# Daysuntil.net
KiCad netlist of a schematic drawn in EAGLE
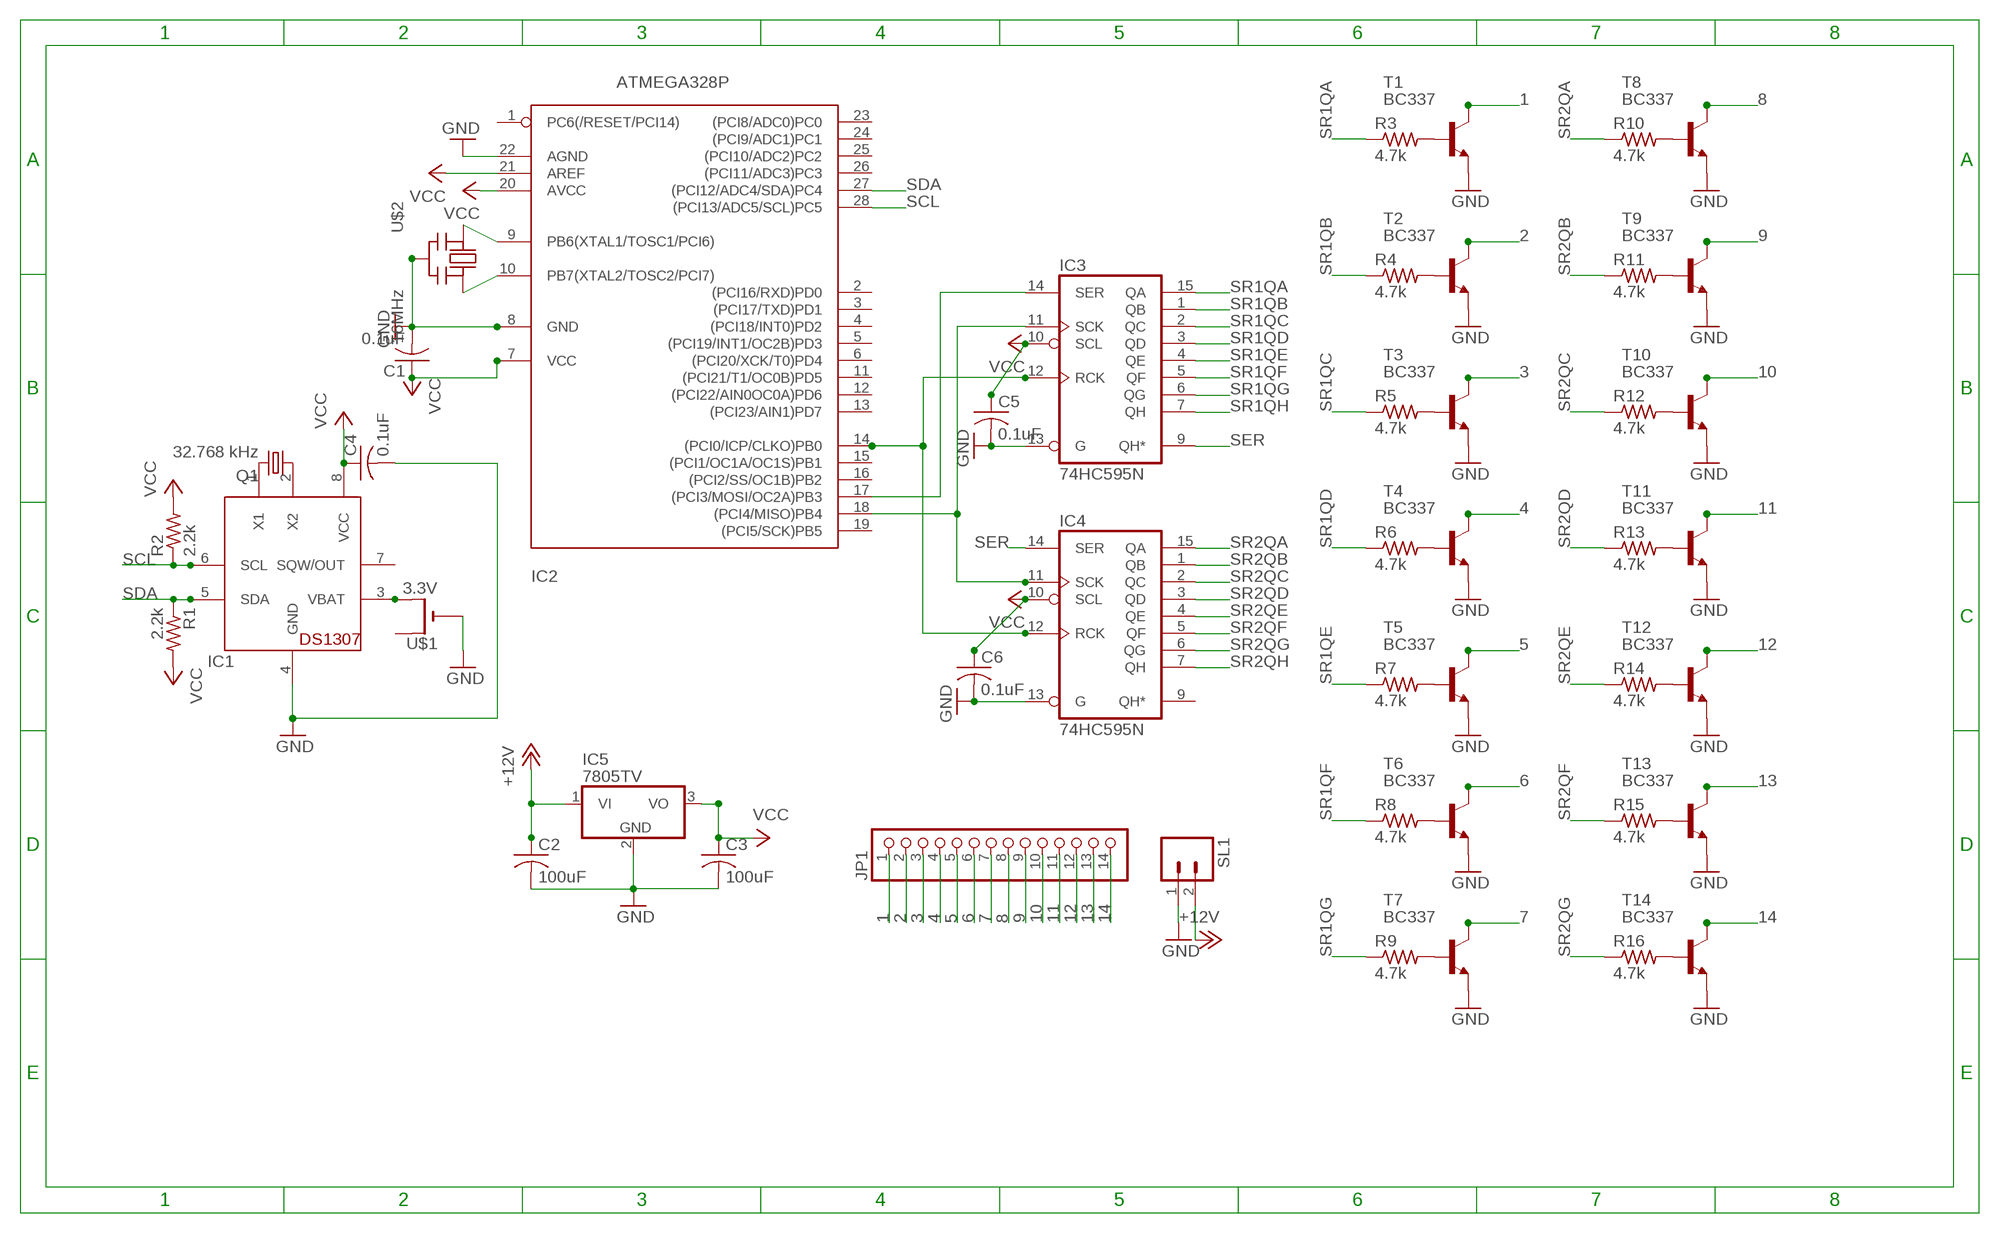
[diagram p0: schematic, sheet 1]

(export (version "E")
  (design (tool "Eeschema 10.0.6"))
  (components
    (comp (ref "C1")
      (value "0.1uF")
      (footprint "eagle-import:C025-030X050")
      (libsource (lib "eagle-import") (part "C-US025-030X050"))
    )
    (comp (ref "C2")
      (value "100uF")
      (footprint "eagle-import:C050-050X075")
      (libsource (lib "eagle-import") (part "C-US050-050X075"))
    )
    (comp (ref "C3")
      (value "100uF")
      (footprint "eagle-import:C050-050X075")
      (libsource (lib "eagle-import") (part "C-US050-050X075"))
    )
    (comp (ref "C4")
      (value "0.1uF")
      (footprint "eagle-import:C025-030X050")
      (libsource (lib "eagle-import") (part "C-US025-030X050"))
    )
    (comp (ref "C5")
      (value "0.1uF")
      (footprint "eagle-import:C025-030X050")
      (libsource (lib "eagle-import") (part "C-US025-030X050"))
    )
    (comp (ref "C6")
      (value "0.1uF")
      (footprint "eagle-import:C025-030X050")
      (libsource (lib "eagle-import") (part "C-US025-030X050"))
    )
    (comp (ref "IC1")
      (value "DS1307")
      (footprint "eagle-import:DIL08")
      (libsource (lib "eagle-import") (part "DS1307"))
    )
    (comp (ref "IC2")
      (value "ATMEGA328P")
      (footprint "eagle-import:DIL28-3")
      (libsource (lib "eagle-import") (part "ATMEGA168P-20"))
    )
    (comp (ref "IC3")
      (value "74HC595N")
      (footprint "eagle-import:DIL16")
      (libsource (lib "eagle-import") (part "74595NHC"))
    )
    (comp (ref "IC4")
      (value "74HC595N")
      (footprint "eagle-import:DIL16")
      (libsource (lib "eagle-import") (part "74595NHC"))
    )
    (comp (ref "IC5")
      (value "7805TV")
      (footprint "eagle-import:TO220V")
      (libsource (lib "eagle-import") (part "78TV05"))
    )
    (comp (ref "JP1")
      (value "PINHD-1X14")
      (footprint "eagle-import:1X14")
      (libsource (lib "eagle-import") (part "PINHD-1X14"))
    )
    (comp (ref "Q1")
      (value "32.768 kHz")
      (footprint "eagle-import:TC38H")
      (libsource (lib "eagle-import") (part "CRYSTALTC38H"))
    )
    (comp (ref "R1")
      (value "2.2k")
      (footprint "eagle-import:0309V")
      (libsource (lib "eagle-import") (part "R-US_0309/V"))
    )
    (comp (ref "R2")
      (value "2.2k")
      (footprint "eagle-import:0309V")
      (libsource (lib "eagle-import") (part "R-US_0309/V"))
    )
    (comp (ref "R3")
      (value "4.7k")
      (footprint "eagle-import:0309V")
      (libsource (lib "eagle-import") (part "R-US_0309/V"))
    )
    (comp (ref "R4")
      (value "4.7k")
      (footprint "eagle-import:0309V")
      (libsource (lib "eagle-import") (part "R-US_0309/V"))
    )
    (comp (ref "R5")
      (value "4.7k")
      (footprint "eagle-import:0309V")
      (libsource (lib "eagle-import") (part "R-US_0309/V"))
    )
    (comp (ref "R6")
      (value "4.7k")
      (footprint "eagle-import:0309V")
      (libsource (lib "eagle-import") (part "R-US_0309/V"))
    )
    (comp (ref "R7")
      (value "4.7k")
      (footprint "eagle-import:0309V")
      (libsource (lib "eagle-import") (part "R-US_0309/V"))
    )
    (comp (ref "R8")
      (value "4.7k")
      (footprint "eagle-import:0309V")
      (libsource (lib "eagle-import") (part "R-US_0309/V"))
    )
    (comp (ref "R9")
      (value "4.7k")
      (footprint "eagle-import:0309V")
      (libsource (lib "eagle-import") (part "R-US_0309/V"))
    )
    (comp (ref "R10")
      (value "4.7k")
      (footprint "eagle-import:0309V")
      (libsource (lib "eagle-import") (part "R-US_0309/V"))
    )
    (comp (ref "R11")
      (value "4.7k")
      (footprint "eagle-import:0309V")
      (libsource (lib "eagle-import") (part "R-US_0309/V"))
    )
    (comp (ref "R12")
      (value "4.7k")
      (footprint "eagle-import:0309V")
      (libsource (lib "eagle-import") (part "R-US_0309/V"))
    )
    (comp (ref "R13")
      (value "4.7k")
      (footprint "eagle-import:0309V")
      (libsource (lib "eagle-import") (part "R-US_0309/V"))
    )
    (comp (ref "R14")
      (value "4.7k")
      (footprint "eagle-import:0309V")
      (libsource (lib "eagle-import") (part "R-US_0309/V"))
    )
    (comp (ref "R15")
      (value "4.7k")
      (footprint "eagle-import:0309V")
      (libsource (lib "eagle-import") (part "R-US_0309/V"))
    )
    (comp (ref "R16")
      (value "4.7k")
      (footprint "eagle-import:0309V")
      (libsource (lib "eagle-import") (part "R-US_0309/V"))
    )
    (comp (ref "SL1")
      (value "M02")
      (footprint "eagle-import:02P")
      (libsource (lib "eagle-import") (part "M02"))
    )
    (comp (ref "T1")
      (value "BC337")
      (footprint "eagle-import:TO92")
      (libsource (lib "eagle-import") (part "BC337"))
    )
    (comp (ref "T2")
      (value "BC337")
      (footprint "eagle-import:TO92")
      (libsource (lib "eagle-import") (part "BC337"))
    )
    (comp (ref "T3")
      (value "BC337")
      (footprint "eagle-import:TO92")
      (libsource (lib "eagle-import") (part "BC337"))
    )
    (comp (ref "T4")
      (value "BC337")
      (footprint "eagle-import:TO92")
      (libsource (lib "eagle-import") (part "BC337"))
    )
    (comp (ref "T5")
      (value "BC337")
      (footprint "eagle-import:TO92")
      (libsource (lib "eagle-import") (part "BC337"))
    )
    (comp (ref "T6")
      (value "BC337")
      (footprint "eagle-import:TO92")
      (libsource (lib "eagle-import") (part "BC337"))
    )
    (comp (ref "T7")
      (value "BC337")
      (footprint "eagle-import:TO92")
      (libsource (lib "eagle-import") (part "BC337"))
    )
    (comp (ref "T8")
      (value "BC337")
      (footprint "eagle-import:TO92")
      (libsource (lib "eagle-import") (part "BC337"))
    )
    (comp (ref "T9")
      (value "BC337")
      (footprint "eagle-import:TO92")
      (libsource (lib "eagle-import") (part "BC337"))
    )
    (comp (ref "T10")
      (value "BC337")
      (footprint "eagle-import:TO92")
      (libsource (lib "eagle-import") (part "BC337"))
    )
    (comp (ref "T11")
      (value "BC337")
      (footprint "eagle-import:TO92")
      (libsource (lib "eagle-import") (part "BC337"))
    )
    (comp (ref "T12")
      (value "BC337")
      (footprint "eagle-import:TO92")
      (libsource (lib "eagle-import") (part "BC337"))
    )
    (comp (ref "T13")
      (value "BC337")
      (footprint "eagle-import:TO92")
      (libsource (lib "eagle-import") (part "BC337"))
    )
    (comp (ref "T14")
      (value "BC337")
      (footprint "eagle-import:TO92")
      (libsource (lib "eagle-import") (part "BC337"))
    )
    (comp (ref "U$1")
      (value "3.3V")
      (footprint "eagle-import:CR1220-THM")
      (libsource (lib "eagle-import") (part "CR1220THM"))
    )
    (comp (ref "U$2")
      (value "16MHz")
      (footprint "eagle-import:CERM_OSC")
      (libsource (lib "eagle-import") (part "CERMOSCILL-THM"))
    )
  )
  (nets
    (net (code "1") (name "+12V") (class "Default")
      (node (ref "C2") (pin "1") (pinfunction "1_1") (pintype "passive"))
      (node (ref "IC5") (pin "1") (pinfunction "VI_1") (pintype "input"))
      (node (ref "SL1") (pin "2") (pinfunction "2_2") (pintype "passive"))
    )
    (net (code "2") (name "/1") (class "Default")
      (node (ref "JP1") (pin "1") (pinfunction "1_1") (pintype "passive"))
      (node (ref "T1") (pin "3") (pinfunction "C_3") (pintype "passive"))
    )
    (net (code "3") (name "/2") (class "Default")
      (node (ref "JP1") (pin "2") (pinfunction "2_2") (pintype "passive"))
      (node (ref "T2") (pin "3") (pinfunction "C_3") (pintype "passive"))
    )
    (net (code "4") (name "/3") (class "Default")
      (node (ref "JP1") (pin "3") (pinfunction "3_3") (pintype "passive"))
      (node (ref "T3") (pin "3") (pinfunction "C_3") (pintype "passive"))
    )
    (net (code "5") (name "/4") (class "Default")
      (node (ref "JP1") (pin "4") (pinfunction "4_4") (pintype "passive"))
      (node (ref "T4") (pin "3") (pinfunction "C_3") (pintype "passive"))
    )
    (net (code "6") (name "/5") (class "Default")
      (node (ref "JP1") (pin "5") (pinfunction "5_5") (pintype "passive"))
      (node (ref "T5") (pin "3") (pinfunction "C_3") (pintype "passive"))
    )
    (net (code "7") (name "/6") (class "Default")
      (node (ref "JP1") (pin "6") (pinfunction "6_6") (pintype "passive"))
      (node (ref "T6") (pin "3") (pinfunction "C_3") (pintype "passive"))
    )
    (net (code "8") (name "/7") (class "Default")
      (node (ref "JP1") (pin "7") (pinfunction "7_7") (pintype "passive"))
      (node (ref "T7") (pin "3") (pinfunction "C_3") (pintype "passive"))
    )
    (net (code "9") (name "/8") (class "Default")
      (node (ref "JP1") (pin "8") (pinfunction "8_8") (pintype "passive"))
      (node (ref "T8") (pin "3") (pinfunction "C_3") (pintype "passive"))
    )
    (net (code "10") (name "/9") (class "Default")
      (node (ref "JP1") (pin "9") (pinfunction "9_9") (pintype "passive"))
      (node (ref "T9") (pin "3") (pinfunction "C_3") (pintype "passive"))
    )
    (net (code "11") (name "/10") (class "Default")
      (node (ref "JP1") (pin "10") (pinfunction "10_10") (pintype "passive"))
      (node (ref "T10") (pin "3") (pinfunction "C_3") (pintype "passive"))
    )
    (net (code "12") (name "/11") (class "Default")
      (node (ref "JP1") (pin "11") (pinfunction "11_11") (pintype "passive"))
      (node (ref "T11") (pin "3") (pinfunction "C_3") (pintype "passive"))
    )
    (net (code "13") (name "/12") (class "Default")
      (node (ref "JP1") (pin "12") (pinfunction "12_12") (pintype "passive"))
      (node (ref "T12") (pin "3") (pinfunction "C_3") (pintype "passive"))
    )
    (net (code "14") (name "/13") (class "Default")
      (node (ref "JP1") (pin "13") (pinfunction "13_13") (pintype "passive"))
      (node (ref "T13") (pin "3") (pinfunction "C_3") (pintype "passive"))
    )
    (net (code "15") (name "/14") (class "Default")
      (node (ref "JP1") (pin "14") (pinfunction "14_14") (pintype "passive"))
      (node (ref "T14") (pin "3") (pinfunction "C_3") (pintype "passive"))
    )
    (net (code "16") (name "/SCL") (class "Default")
      (node (ref "IC1") (pin "6") (pinfunction "SCL_6") (pintype "bidirectional"))
      (node (ref "IC2") (pin "28") (pinfunction "(PCI13/ADC5/SCL)PC5_28") (pintype "bidirectional"))
      (node (ref "R2") (pin "1") (pinfunction "1_1") (pintype "passive"))
    )
    (net (code "17") (name "/SDA") (class "Default")
      (node (ref "IC1") (pin "5") (pinfunction "SDA_5") (pintype "bidirectional"))
      (node (ref "IC2") (pin "27") (pinfunction "(PCI12/ADC4/SDA)PC4_27") (pintype "bidirectional"))
      (node (ref "R1") (pin "1") (pinfunction "1_1") (pintype "passive"))
    )
    (net (code "18") (name "/SER") (class "Default")
      (node (ref "IC3") (pin "9") (pinfunction "QH*_9") (pintype "tri_state"))
      (node (ref "IC4") (pin "14") (pinfunction "SER_14") (pintype "input"))
    )
    (net (code "19") (name "/SR1QA") (class "Default")
      (node (ref "IC3") (pin "15") (pinfunction "QA_15") (pintype "tri_state"))
      (node (ref "R3") (pin "1") (pinfunction "1_1") (pintype "passive"))
    )
    (net (code "20") (name "/SR1QB") (class "Default")
      (node (ref "IC3") (pin "1") (pinfunction "QB_1") (pintype "tri_state"))
      (node (ref "R4") (pin "1") (pinfunction "1_1") (pintype "passive"))
    )
    (net (code "21") (name "/SR1QC") (class "Default")
      (node (ref "IC3") (pin "2") (pinfunction "QC_2") (pintype "tri_state"))
      (node (ref "R5") (pin "1") (pinfunction "1_1") (pintype "passive"))
    )
    (net (code "22") (name "/SR1QD") (class "Default")
      (node (ref "IC3") (pin "3") (pinfunction "QD_3") (pintype "tri_state"))
      (node (ref "R6") (pin "1") (pinfunction "1_1") (pintype "passive"))
    )
    (net (code "23") (name "/SR1QE") (class "Default")
      (node (ref "IC3") (pin "4") (pinfunction "QE_4") (pintype "tri_state"))
      (node (ref "R7") (pin "1") (pinfunction "1_1") (pintype "passive"))
    )
    (net (code "24") (name "/SR1QF") (class "Default")
      (node (ref "IC3") (pin "5") (pinfunction "QF_5") (pintype "tri_state"))
      (node (ref "R8") (pin "1") (pinfunction "1_1") (pintype "passive"))
    )
    (net (code "25") (name "/SR1QG") (class "Default")
      (node (ref "IC3") (pin "6") (pinfunction "QG_6") (pintype "tri_state"))
      (node (ref "R9") (pin "1") (pinfunction "1_1") (pintype "passive"))
    )
    (net (code "26") (name "/SR1QH") (class "Default")
      (node (ref "IC3") (pin "7") (pinfunction "QH_7") (pintype "tri_state"))
    )
    (net (code "27") (name "/SR2QA") (class "Default")
      (node (ref "IC4") (pin "15") (pinfunction "QA_15") (pintype "tri_state"))
      (node (ref "R10") (pin "1") (pinfunction "1_1") (pintype "passive"))
    )
    (net (code "28") (name "/SR2QB") (class "Default")
      (node (ref "IC4") (pin "1") (pinfunction "QB_1") (pintype "tri_state"))
      (node (ref "R11") (pin "1") (pinfunction "1_1") (pintype "passive"))
    )
    (net (code "29") (name "/SR2QC") (class "Default")
      (node (ref "IC4") (pin "2") (pinfunction "QC_2") (pintype "tri_state"))
      (node (ref "R12") (pin "1") (pinfunction "1_1") (pintype "passive"))
    )
    (net (code "30") (name "/SR2QD") (class "Default")
      (node (ref "IC4") (pin "3") (pinfunction "QD_3") (pintype "tri_state"))
      (node (ref "R13") (pin "1") (pinfunction "1_1") (pintype "passive"))
    )
    (net (code "31") (name "/SR2QE") (class "Default")
      (node (ref "IC4") (pin "4") (pinfunction "QE_4") (pintype "tri_state"))
      (node (ref "R14") (pin "1") (pinfunction "1_1") (pintype "passive"))
    )
    (net (code "32") (name "/SR2QF") (class "Default")
      (node (ref "IC4") (pin "5") (pinfunction "QF_5") (pintype "tri_state"))
      (node (ref "R15") (pin "1") (pinfunction "1_1") (pintype "passive"))
    )
    (net (code "33") (name "/SR2QG") (class "Default")
      (node (ref "IC4") (pin "6") (pinfunction "QG_6") (pintype "tri_state"))
      (node (ref "R16") (pin "1") (pinfunction "1_1") (pintype "passive"))
    )
    (net (code "34") (name "/SR2QH") (class "Default")
      (node (ref "IC4") (pin "7") (pinfunction "QH_7") (pintype "tri_state"))
    )
    (net (code "35") (name "GND") (class "Default")
      (node (ref "C1") (pin "2") (pinfunction "2_2") (pintype "passive"))
      (node (ref "C2") (pin "2") (pinfunction "2_2") (pintype "passive"))
      (node (ref "C3") (pin "2") (pinfunction "2_2") (pintype "passive"))
      (node (ref "C4") (pin "2") (pinfunction "2_2") (pintype "passive"))
      (node (ref "C5") (pin "2") (pinfunction "2_2") (pintype "passive"))
      (node (ref "C6") (pin "2") (pinfunction "2_2") (pintype "passive"))
      (node (ref "IC1") (pin "4") (pinfunction "GND_4") (pintype "power_in"))
      (node (ref "IC2") (pin "22") (pinfunction "AGND_22") (pintype "bidirectional"))
      (node (ref "IC2") (pin "8") (pinfunction "GND_8") (pintype "bidirectional"))
      (node (ref "IC3") (pin "13") (pinfunction "G_13") (pintype "input"))
      (node (ref "IC4") (pin "13") (pinfunction "G_13") (pintype "input"))
      (node (ref "IC5") (pin "2") (pinfunction "GND_2") (pintype "passive"))
      (node (ref "SL1") (pin "1") (pinfunction "1_1") (pintype "passive"))
      (node (ref "T1") (pin "1") (pinfunction "E_1") (pintype "passive"))
      (node (ref "T10") (pin "1") (pinfunction "E_1") (pintype "passive"))
      (node (ref "T11") (pin "1") (pinfunction "E_1") (pintype "passive"))
      (node (ref "T12") (pin "1") (pinfunction "E_1") (pintype "passive"))
      (node (ref "T13") (pin "1") (pinfunction "E_1") (pintype "passive"))
      (node (ref "T14") (pin "1") (pinfunction "E_1") (pintype "passive"))
      (node (ref "T2") (pin "1") (pinfunction "E_1") (pintype "passive"))
      (node (ref "T3") (pin "1") (pinfunction "E_1") (pintype "passive"))
      (node (ref "T4") (pin "1") (pinfunction "E_1") (pintype "passive"))
      (node (ref "T5") (pin "1") (pinfunction "E_1") (pintype "passive"))
      (node (ref "T6") (pin "1") (pinfunction "E_1") (pintype "passive"))
      (node (ref "T7") (pin "1") (pinfunction "E_1") (pintype "passive"))
      (node (ref "T8") (pin "1") (pinfunction "E_1") (pintype "passive"))
      (node (ref "T9") (pin "1") (pinfunction "E_1") (pintype "passive"))
      (node (ref "U$1") (pin "-") (pinfunction "-_-") (pintype "passive"))
      (node (ref "U$2") (pin "P$2") (pinfunction "GND_P$2") (pintype "bidirectional"))
    )
    (net (code "36") (name "Net-(IC1-VBAT)") (class "Default")
      (node (ref "IC1") (pin "3") (pinfunction "VBAT_3") (pintype "power_in"))
      (node (ref "U$1") (pin "+2") (pinfunction "+1_+2") (pintype "passive"))
    )
    (net (code "37") (name "Net-(IC1-X1)") (class "Default")
      (node (ref "IC1") (pin "1") (pinfunction "X1_1") (pintype "passive"))
      (node (ref "Q1") (pin "2") (pinfunction "2_2") (pintype "passive"))
    )
    (net (code "38") (name "Net-(IC1-X2)") (class "Default")
      (node (ref "IC1") (pin "2") (pinfunction "X2_2") (pintype "passive"))
      (node (ref "Q1") (pin "1") (pinfunction "1_1") (pintype "passive"))
    )
    (net (code "39") (name "Net-(IC2-(PCI0{slash}ICP{slash}CLKO)PB0)") (class "Default")
      (node (ref "IC2") (pin "14") (pinfunction "(PCI0/ICP/CLKO)PB0_14") (pintype "bidirectional"))
      (node (ref "IC3") (pin "12") (pinfunction "RCK_12") (pintype "input"))
      (node (ref "IC4") (pin "12") (pinfunction "RCK_12") (pintype "input"))
    )
    (net (code "40") (name "Net-(IC2-(PCI3{slash}MOSI{slash}OC2A)PB3)") (class "Default")
      (node (ref "IC2") (pin "17") (pinfunction "(PCI3/MOSI/OC2A)PB3_17") (pintype "bidirectional"))
      (node (ref "IC3") (pin "14") (pinfunction "SER_14") (pintype "input"))
    )
    (net (code "41") (name "Net-(IC2-(PCI4{slash}MISO)PB4)") (class "Default")
      (node (ref "IC2") (pin "18") (pinfunction "(PCI4/MISO)PB4_18") (pintype "bidirectional"))
      (node (ref "IC3") (pin "11") (pinfunction "SCK_11") (pintype "input"))
      (node (ref "IC4") (pin "11") (pinfunction "SCK_11") (pintype "input"))
    )
    (net (code "42") (name "Net-(IC2-PB6(XTAL1{slash}TOSC1{slash}PCI6))") (class "Default")
      (node (ref "IC2") (pin "9") (pinfunction "PB6(XTAL1/TOSC1/PCI6)_9") (pintype "bidirectional"))
      (node (ref "U$2") (pin "P$1") (pinfunction "IN_P$1") (pintype "bidirectional"))
    )
    (net (code "43") (name "Net-(IC2-PB7(XTAL2{slash}TOSC2{slash}PCI7))") (class "Default")
      (node (ref "IC2") (pin "10") (pinfunction "PB7(XTAL2/TOSC2/PCI7)_10") (pintype "bidirectional"))
      (node (ref "U$2") (pin "P$3") (pinfunction "OUT_P$3") (pintype "bidirectional"))
    )
    (net (code "44") (name "Net-(T1-B)") (class "Default")
      (node (ref "R3") (pin "2") (pinfunction "2_2") (pintype "passive"))
      (node (ref "T1") (pin "2") (pinfunction "B_2") (pintype "passive"))
    )
    (net (code "45") (name "Net-(T2-B)") (class "Default")
      (node (ref "R4") (pin "2") (pinfunction "2_2") (pintype "passive"))
      (node (ref "T2") (pin "2") (pinfunction "B_2") (pintype "passive"))
    )
    (net (code "46") (name "Net-(T3-B)") (class "Default")
      (node (ref "R5") (pin "2") (pinfunction "2_2") (pintype "passive"))
      (node (ref "T3") (pin "2") (pinfunction "B_2") (pintype "passive"))
    )
    (net (code "47") (name "Net-(T4-B)") (class "Default")
      (node (ref "R6") (pin "2") (pinfunction "2_2") (pintype "passive"))
      (node (ref "T4") (pin "2") (pinfunction "B_2") (pintype "passive"))
    )
    (net (code "48") (name "Net-(T5-B)") (class "Default")
      (node (ref "R7") (pin "2") (pinfunction "2_2") (pintype "passive"))
      (node (ref "T5") (pin "2") (pinfunction "B_2") (pintype "passive"))
    )
    (net (code "49") (name "Net-(T6-B)") (class "Default")
      (node (ref "R8") (pin "2") (pinfunction "2_2") (pintype "passive"))
      (node (ref "T6") (pin "2") (pinfunction "B_2") (pintype "passive"))
    )
    (net (code "50") (name "Net-(T7-B)") (class "Default")
      (node (ref "R9") (pin "2") (pinfunction "2_2") (pintype "passive"))
      (node (ref "T7") (pin "2") (pinfunction "B_2") (pintype "passive"))
    )
    (net (code "51") (name "Net-(T8-B)") (class "Default")
      (node (ref "R10") (pin "2") (pinfunction "2_2") (pintype "passive"))
      (node (ref "T8") (pin "2") (pinfunction "B_2") (pintype "passive"))
    )
    (net (code "52") (name "Net-(T9-B)") (class "Default")
      (node (ref "R11") (pin "2") (pinfunction "2_2") (pintype "passive"))
      (node (ref "T9") (pin "2") (pinfunction "B_2") (pintype "passive"))
    )
    (net (code "53") (name "Net-(T10-B)") (class "Default")
      (node (ref "R12") (pin "2") (pinfunction "2_2") (pintype "passive"))
      (node (ref "T10") (pin "2") (pinfunction "B_2") (pintype "passive"))
    )
    (net (code "54") (name "Net-(T11-B)") (class "Default")
      (node (ref "R13") (pin "2") (pinfunction "2_2") (pintype "passive"))
      (node (ref "T11") (pin "2") (pinfunction "B_2") (pintype "passive"))
    )
    (net (code "55") (name "Net-(T12-B)") (class "Default")
      (node (ref "R14") (pin "2") (pinfunction "2_2") (pintype "passive"))
      (node (ref "T12") (pin "2") (pinfunction "B_2") (pintype "passive"))
    )
    (net (code "56") (name "Net-(T13-B)") (class "Default")
      (node (ref "R15") (pin "2") (pinfunction "2_2") (pintype "passive"))
      (node (ref "T13") (pin "2") (pinfunction "B_2") (pintype "passive"))
    )
    (net (code "57") (name "Net-(T14-B)") (class "Default")
      (node (ref "R16") (pin "2") (pinfunction "2_2") (pintype "passive"))
      (node (ref "T14") (pin "2") (pinfunction "B_2") (pintype "passive"))
    )
    (net (code "58") (name "VCC") (class "Default")
      (node (ref "C1") (pin "1") (pinfunction "1_1") (pintype "passive"))
      (node (ref "C3") (pin "1") (pinfunction "1_1") (pintype "passive"))
      (node (ref "C4") (pin "1") (pinfunction "1_1") (pintype "passive"))
      (node (ref "C5") (pin "1") (pinfunction "1_1") (pintype "passive"))
      (node (ref "C6") (pin "1") (pinfunction "1_1") (pintype "passive"))
      (node (ref "IC1") (pin "8") (pinfunction "VCC_8") (pintype "power_in"))
      (node (ref "IC2") (pin "20") (pinfunction "AVCC_20") (pintype "bidirectional"))
      (node (ref "IC2") (pin "21") (pinfunction "AREF_21") (pintype "bidirectional"))
      (node (ref "IC2") (pin "7") (pinfunction "VCC_7") (pintype "bidirectional"))
      (node (ref "IC3") (pin "10") (pinfunction "SCL_10") (pintype "input"))
      (node (ref "IC4") (pin "10") (pinfunction "SCL_10") (pintype "input"))
      (node (ref "IC5") (pin "3") (pinfunction "VO_3") (pintype "passive"))
      (node (ref "R1") (pin "2") (pinfunction "2_2") (pintype "passive"))
      (node (ref "R2") (pin "2") (pinfunction "2_2") (pintype "passive"))
    )
    (net (code "59") (name "unconnected-(IC1-SQW{slash}OUT-Pad7)") (class "Default")
      (node (ref "IC1") (pin "7") (pinfunction "SQW/OUT_7") (pintype "bidirectional"))
    )
    (net (code "60") (name "unconnected-(IC2-(PCI1{slash}OC1A{slash}OC1S)PB1-Pad15)") (class "Default")
      (node (ref "IC2") (pin "15") (pinfunction "(PCI1/OC1A/OC1S)PB1_15") (pintype "bidirectional"))
    )
    (net (code "61") (name "unconnected-(IC2-(PCI2{slash}SS{slash}OC1B)PB2-Pad16)") (class "Default")
      (node (ref "IC2") (pin "16") (pinfunction "(PCI2/SS/OC1B)PB2_16") (pintype "bidirectional"))
    )
    (net (code "62") (name "unconnected-(IC2-(PCI5{slash}SCK)PB5-Pad19)") (class "Default")
      (node (ref "IC2") (pin "19") (pinfunction "(PCI5/SCK)PB5_19") (pintype "bidirectional"))
    )
    (net (code "63") (name "unconnected-(IC2-(PCI8{slash}ADC0)PC0-Pad23)") (class "Default")
      (node (ref "IC2") (pin "23") (pinfunction "(PCI8/ADC0)PC0_23") (pintype "bidirectional"))
    )
    (net (code "64") (name "unconnected-(IC2-(PCI9{slash}ADC1)PC1-Pad24)") (class "Default")
      (node (ref "IC2") (pin "24") (pinfunction "(PCI9/ADC1)PC1_24") (pintype "bidirectional"))
    )
    (net (code "65") (name "unconnected-(IC2-(PCI10{slash}ADC2)PC2-Pad25)") (class "Default")
      (node (ref "IC2") (pin "25") (pinfunction "(PCI10/ADC2)PC2_25") (pintype "bidirectional"))
    )
    (net (code "66") (name "unconnected-(IC2-(PCI11{slash}ADC3)PC3-Pad26)") (class "Default")
      (node (ref "IC2") (pin "26") (pinfunction "(PCI11/ADC3)PC3_26") (pintype "bidirectional"))
    )
    (net (code "67") (name "unconnected-(IC2-(PCI16{slash}RXD)PD0-Pad2)") (class "Default")
      (node (ref "IC2") (pin "2") (pinfunction "(PCI16/RXD)PD0_2") (pintype "bidirectional"))
    )
    (net (code "68") (name "unconnected-(IC2-(PCI17{slash}TXD)PD1-Pad3)") (class "Default")
      (node (ref "IC2") (pin "3") (pinfunction "(PCI17/TXD)PD1_3") (pintype "bidirectional"))
    )
    (net (code "69") (name "unconnected-(IC2-(PCI18{slash}INT0)PD2-Pad4)") (class "Default")
      (node (ref "IC2") (pin "4") (pinfunction "(PCI18/INT0)PD2_4") (pintype "bidirectional"))
    )
    (net (code "70") (name "unconnected-(IC2-(PCI19{slash}INT1{slash}OC2B)PD3-Pad5)") (class "Default")
      (node (ref "IC2") (pin "5") (pinfunction "(PCI19/INT1/OC2B)PD3_5") (pintype "bidirectional"))
    )
    (net (code "71") (name "unconnected-(IC2-(PCI20{slash}XCK{slash}T0)PD4-Pad6)") (class "Default")
      (node (ref "IC2") (pin "6") (pinfunction "(PCI20/XCK/T0)PD4_6") (pintype "bidirectional"))
    )
    (net (code "72") (name "unconnected-(IC2-(PCI21{slash}T1{slash}OC0B)PD5-Pad11)") (class "Default")
      (node (ref "IC2") (pin "11") (pinfunction "(PCI21/T1/OC0B)PD5_11") (pintype "bidirectional"))
    )
    (net (code "73") (name "unconnected-(IC2-(PCI22{slash}AIN0OC0A)PD6-Pad12)") (class "Default")
      (node (ref "IC2") (pin "12") (pinfunction "(PCI22/AIN0OC0A)PD6_12") (pintype "bidirectional"))
    )
    (net (code "74") (name "unconnected-(IC2-(PCI23{slash}AIN1)PD7-Pad13)") (class "Default")
      (node (ref "IC2") (pin "13") (pinfunction "(PCI23/AIN1)PD7_13") (pintype "bidirectional"))
    )
    (net (code "75") (name "unconnected-(IC2-PC6({slash}RESET{slash}PCI14)-Pad1)") (class "Default")
      (node (ref "IC2") (pin "1") (pinfunction "PC6(/RESET/PCI14)_1") (pintype "bidirectional"))
    )
    (net (code "76") (name "unconnected-(IC4A-QH*-Pad9)") (class "Default")
      (node (ref "IC4") (pin "9") (pinfunction "QH*_9") (pintype "tri_state"))
    )
    (net (code "77") (name "unconnected-(U$1-+-Pad+1)") (class "Default")
      (node (ref "U$1") (pin "+1") (pinfunction "+_+1") (pintype "passive"))
    )
  )
)
